# Challenger-2040.net
KiCad netlist of a schematic drawn in EAGLE
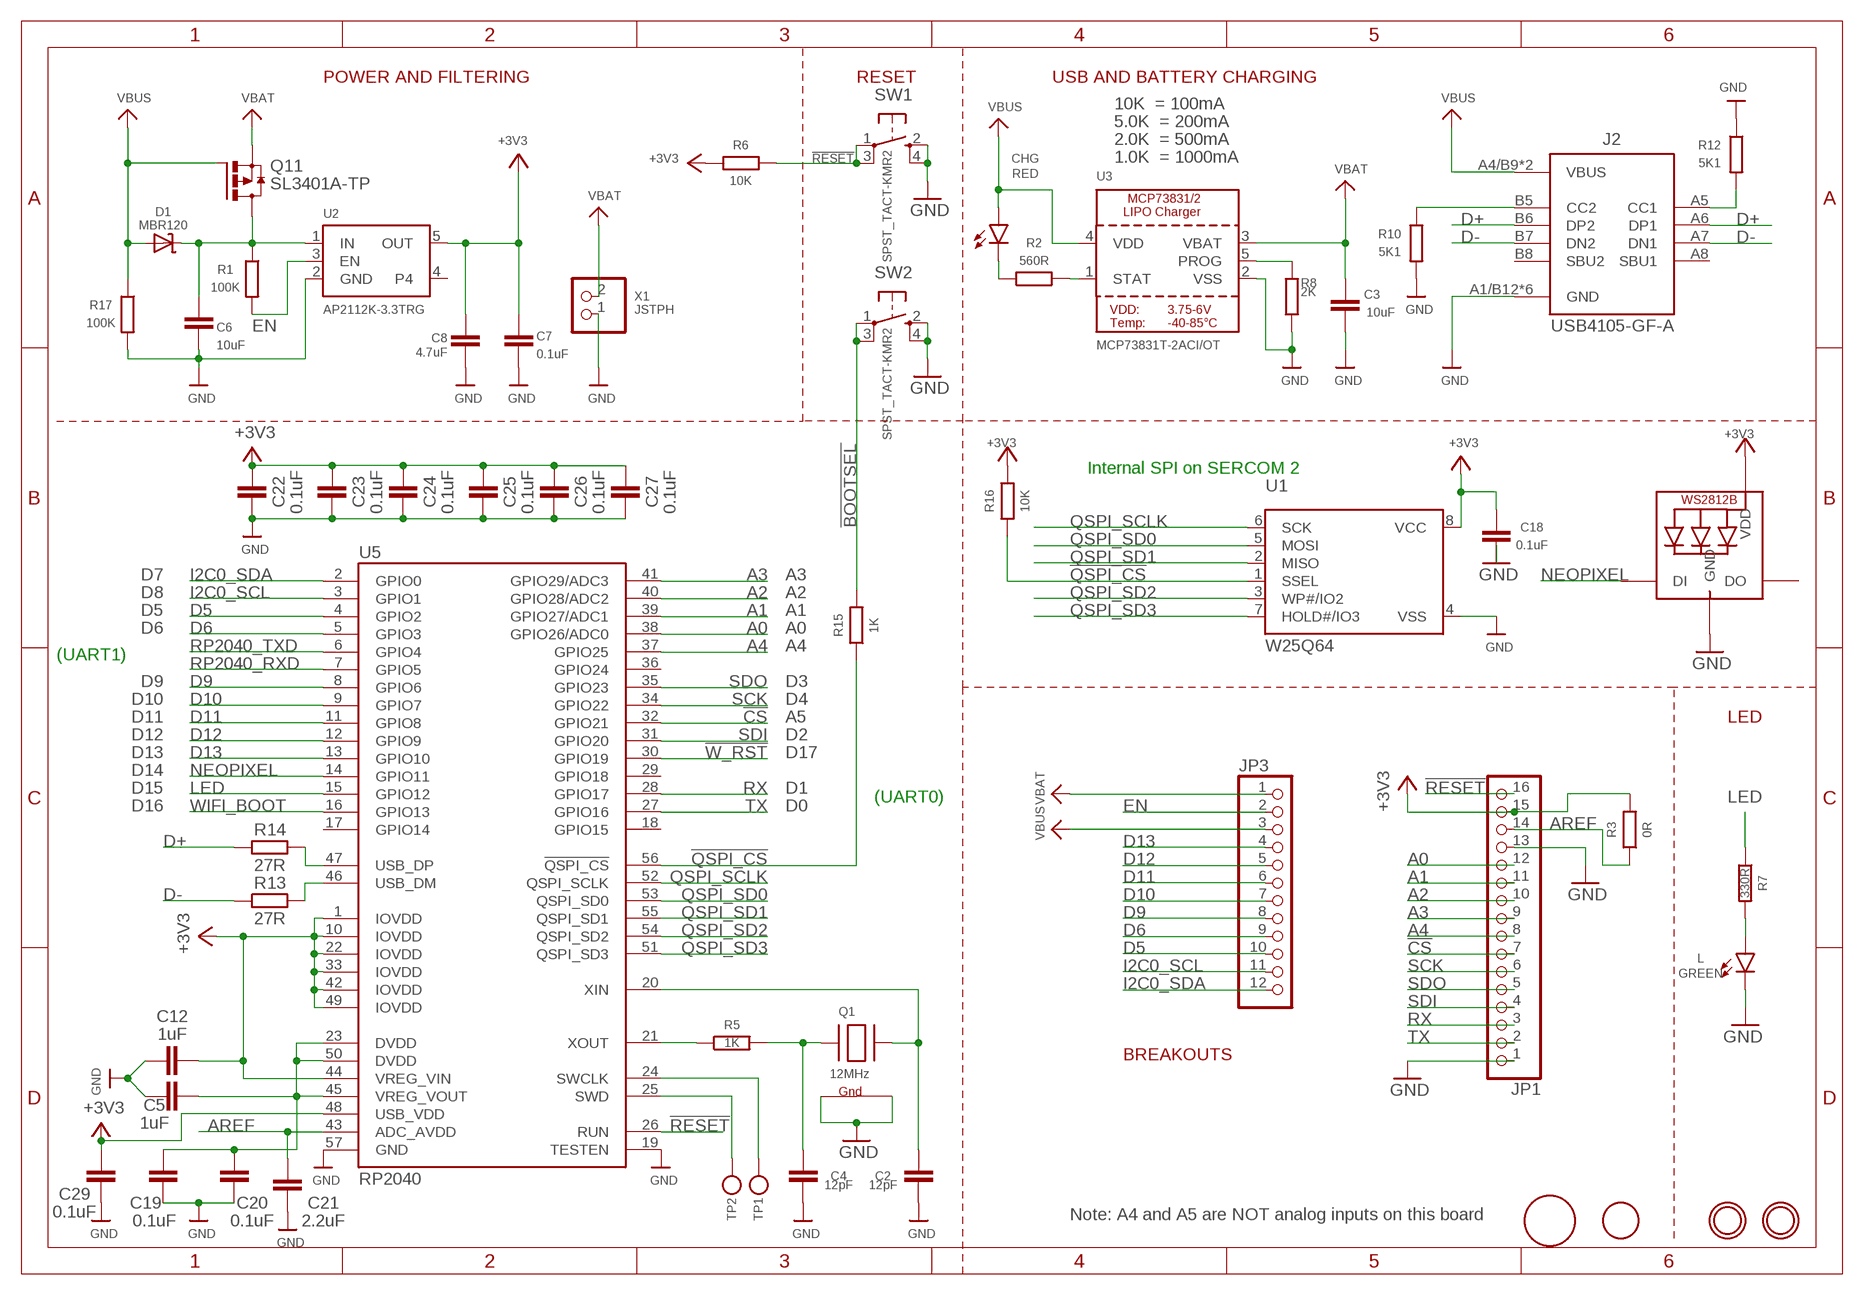
[diagram p0: schematic, sheet 1]
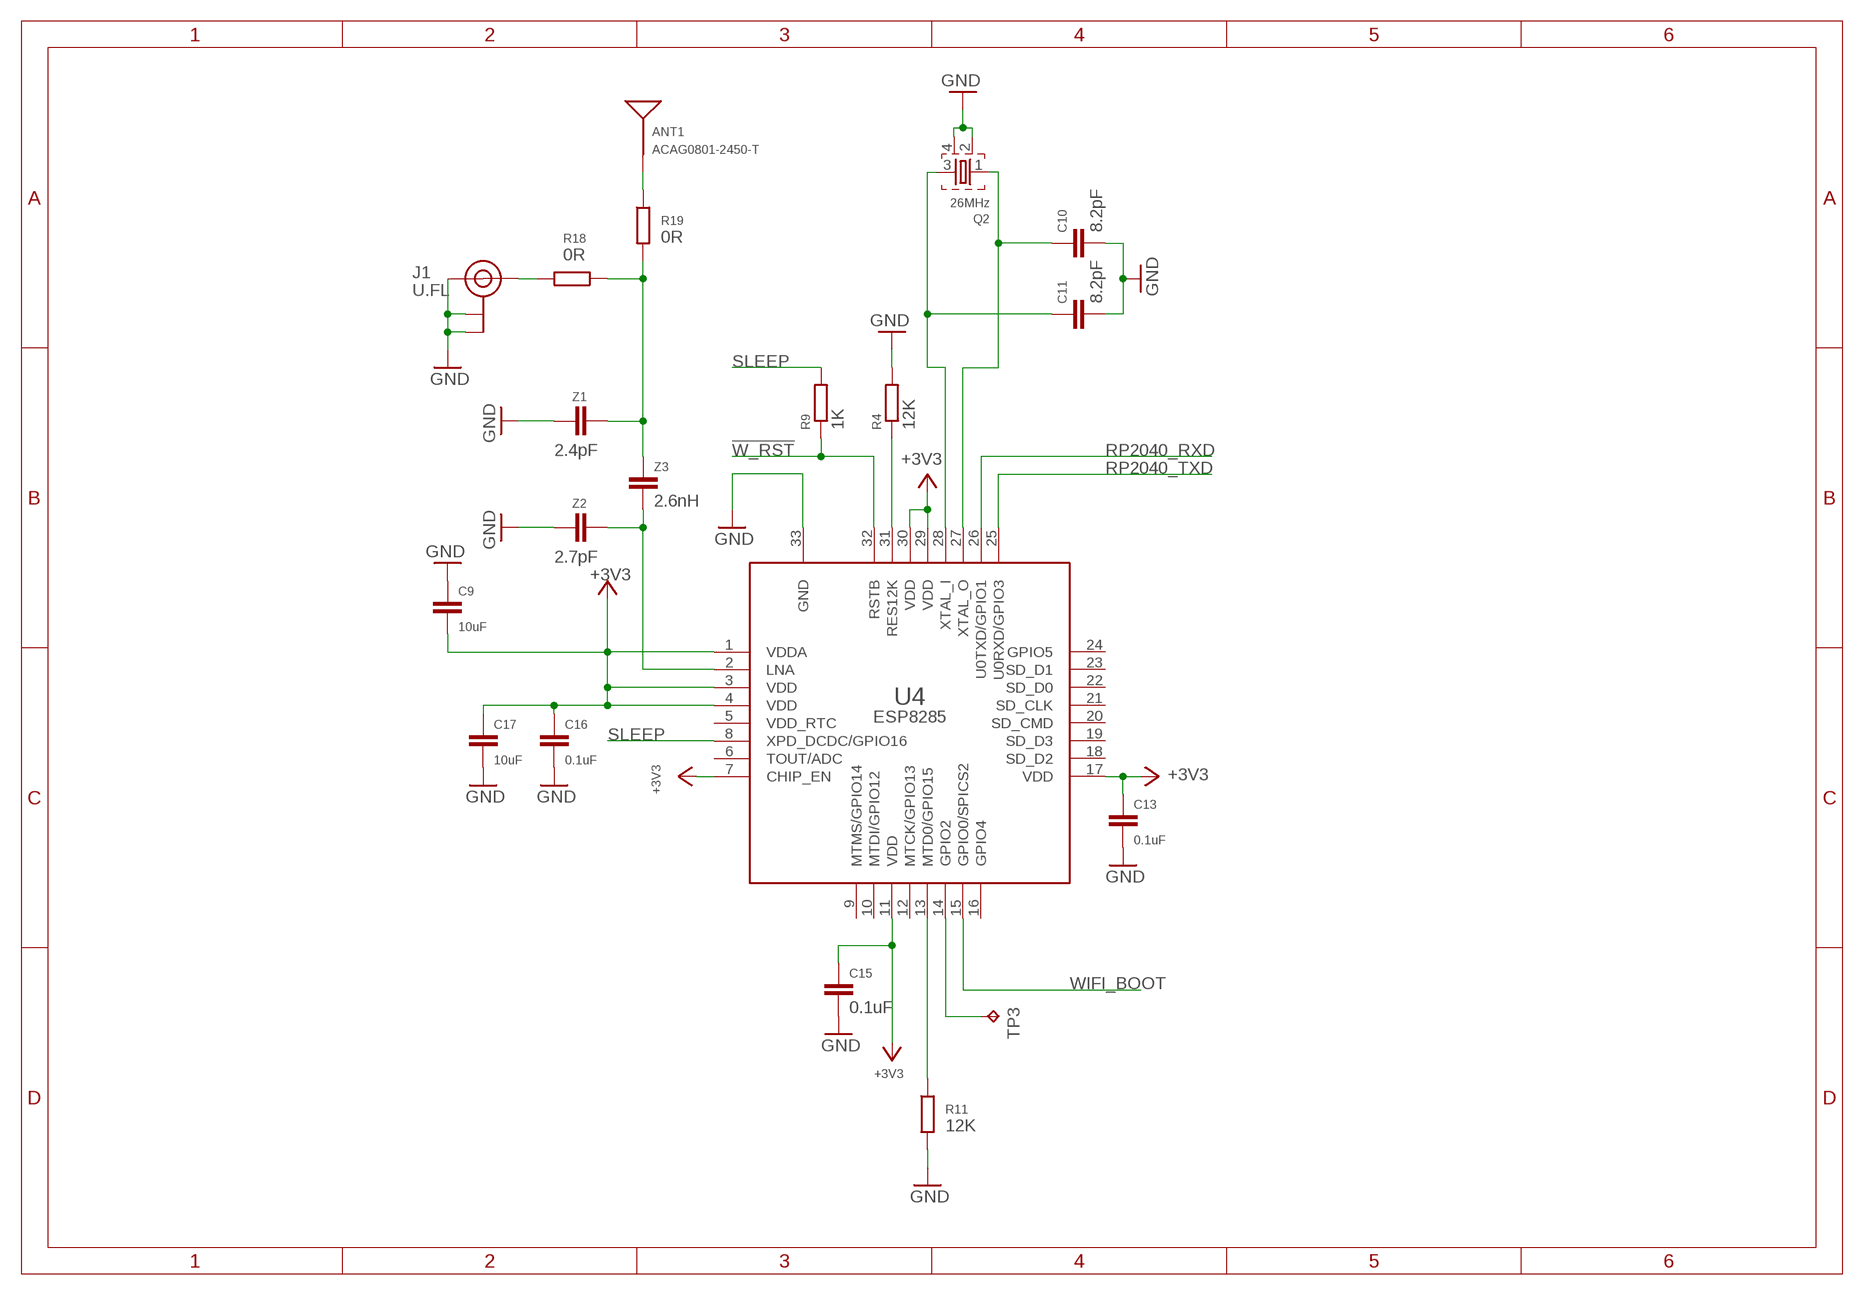
[diagram p1: schematic, sheet 2]

(export (version "E")
  (design (tool "Eeschema 10.0.6"))
  (components
    (comp (ref "C2")
      (value "12pF")
      (footprint "eagle-import:CAPC1005X60")
      (libsource (lib "eagle-import") (part "CCHIP-0402(1005-METRIC)_"))
    )
    (comp (ref "C3")
      (value "10uF")
      (footprint "eagle-import:CAPC1608X85")
      (libsource (lib "eagle-import") (part "CCHIP-0603(1608-METRIC)_"))
    )
    (comp (ref "C4")
      (value "12pF")
      (footprint "eagle-import:CAPC1005X60")
      (libsource (lib "eagle-import") (part "CCHIP-0402(1005-METRIC)_"))
    )
    (comp (ref "C5")
      (value "1uF")
      (footprint "eagle-import:CAPC1005X60")
      (libsource (lib "eagle-import") (part "CCHIP-0402(1005-METRIC)_"))
    )
    (comp (ref "C6")
      (value "10uF")
      (footprint "eagle-import:CAPC1608X85")
      (libsource (lib "eagle-import") (part "CCHIP-0603(1608-METRIC)_"))
    )
    (comp (ref "C7")
      (value "0.1uF")
      (footprint "eagle-import:CAPC1005X60")
      (libsource (lib "eagle-import") (part "CCHIP-0402(1005-METRIC)_"))
    )
    (comp (ref "C8")
      (value "4.7uF")
      (footprint "eagle-import:CAPC1005X60")
      (libsource (lib "eagle-import") (part "CCHIP-0402(1005-METRIC)_"))
    )
    (comp (ref "C12")
      (value "1uF")
      (footprint "eagle-import:CAPC1005X60")
      (libsource (lib "eagle-import") (part "CCHIP-0402(1005-METRIC)_"))
    )
    (comp (ref "C18")
      (value "0.1uF")
      (footprint "eagle-import:CAPC1005X60")
      (libsource (lib "eagle-import") (part "CCHIP-0402(1005-METRIC)_"))
    )
    (comp (ref "C19")
      (value "0.1uF")
      (footprint "eagle-import:CAPC1005X60")
      (libsource (lib "eagle-import") (part "CCHIP-0402(1005-METRIC)_"))
    )
    (comp (ref "C20")
      (value "0.1uF")
      (footprint "eagle-import:CAPC1005X60")
      (libsource (lib "eagle-import") (part "CCHIP-0402(1005-METRIC)_"))
    )
    (comp (ref "C21")
      (value "2.2uF")
      (footprint "eagle-import:CAPC1005X60")
      (libsource (lib "eagle-import") (part "CCHIP-0402(1005-METRIC)_"))
    )
    (comp (ref "C22")
      (value "0.1uF")
      (footprint "eagle-import:CAPC1005X60")
      (libsource (lib "eagle-import") (part "CCHIP-0402(1005-METRIC)_"))
    )
    (comp (ref "C23")
      (value "0.1uF")
      (footprint "eagle-import:CAPC1005X60")
      (libsource (lib "eagle-import") (part "CCHIP-0402(1005-METRIC)_"))
    )
    (comp (ref "C24")
      (value "0.1uF")
      (footprint "eagle-import:CAPC1005X60")
      (libsource (lib "eagle-import") (part "CCHIP-0402(1005-METRIC)_"))
    )
    (comp (ref "C25")
      (value "0.1uF")
      (footprint "eagle-import:CAPC1005X60")
      (libsource (lib "eagle-import") (part "CCHIP-0402(1005-METRIC)_"))
    )
    (comp (ref "C26")
      (value "0.1uF")
      (footprint "eagle-import:CAPC1005X60")
      (libsource (lib "eagle-import") (part "CCHIP-0402(1005-METRIC)_"))
    )
    (comp (ref "C27")
      (value "0.1uF")
      (footprint "eagle-import:CAPC1005X60")
      (libsource (lib "eagle-import") (part "CCHIP-0402(1005-METRIC)_"))
    )
    (comp (ref "C29")
      (value "0.1uF")
      (footprint "eagle-import:CAPC1005X60")
      (libsource (lib "eagle-import") (part "CCHIP-0402(1005-METRIC)_"))
    )
    (comp (ref "CHG")
      (value "RED")
      (footprint "eagle-import:CHIPLED_0603")
      (libsource (lib "eagle-import") (part "LEDCHIPLED_0603"))
    )
    (comp (ref "D1")
      (value "MBR120")
      (footprint "eagle-import:SOD-123")
      (libsource (lib "eagle-import") (part "DIODE-SCHOTTKYSOD-123"))
    )
    (comp (ref "J2")
      (value "USB4105-GF-A")
      (footprint "eagle-import:GCT_USB4105-GF-A")
      (fields (field (name "MF") "GCT"))
      (libsource (lib "eagle-import") (part "USB4105-GF-A"))
    )
    (comp (ref "JP1")
      (value "HEADER-1X16ROUND")
      (footprint "eagle-import:1X16_ROUND")
      (libsource (lib "eagle-import") (part "HEADER-1X16ROUND"))
    )
    (comp (ref "JP3")
      (value "HEADER-1X12")
      (footprint "eagle-import:1X12_ROUND")
      (libsource (lib "eagle-import") (part "HEADER-1X12"))
    )
    (comp (ref "L")
      (value "GREEN")
      (footprint "eagle-import:CHIPLED_0603")
      (libsource (lib "eagle-import") (part "LEDCHIPLED_0603"))
    )
    (comp (ref "LED1")
      (value "SK6812MINI-B")
      (footprint "eagle-import:LED3535")
      (libsource (lib "eagle-import") (part "WS2812B3535"))
    )
    (comp (ref "LOGO1")
      (value "CHALENGER-11MM")
      (footprint "eagle-import:CHALLENGER")
      (libsource (lib "eagle-import") (part "CHALENGER-11MM"))
    )
    (comp (ref "Q1")
      (value "12MHz")
      (footprint "eagle-import:NX3225")
      (libsource (lib "eagle-import") (part "XTAL-4-3225"))
    )
    (comp (ref "Q11")
      (value "SL3401A-TP")
      (footprint "eagle-import:SUPER-SOT3")
      (libsource (lib "eagle-import") (part "FDN360P"))
    )
    (comp (ref "R1")
      (value "100K")
      (footprint "eagle-import:RESC1005X40")
      (libsource (lib "eagle-import") (part "RCHIP-0402(1005-METRIC)_"))
    )
    (comp (ref "R2")
      (value "560R")
      (footprint "eagle-import:RESC1005X40")
      (libsource (lib "eagle-import") (part "RCHIP-0402(1005-METRIC)_"))
    )
    (comp (ref "R3")
      (value "0R")
      (footprint "eagle-import:RESC1005X40")
      (libsource (lib "eagle-import") (part "RCHIP-0402(1005-METRIC)_"))
    )
    (comp (ref "R5")
      (value "1K")
      (footprint "eagle-import:RESC1005X40")
      (libsource (lib "eagle-import") (part "RCHIP-0402(1005-METRIC)_"))
    )
    (comp (ref "R6")
      (value "10K")
      (footprint "eagle-import:RESC1005X40")
      (libsource (lib "eagle-import") (part "RCHIP-0402(1005-METRIC)_"))
    )
    (comp (ref "R7")
      (value "330R")
      (footprint "eagle-import:RESC1005X40")
      (libsource (lib "eagle-import") (part "RCHIP-0402(1005-METRIC)_"))
    )
    (comp (ref "R8")
      (value "2K")
      (footprint "eagle-import:RESC1005X40")
      (libsource (lib "eagle-import") (part "RCHIP-0402(1005-METRIC)_"))
    )
    (comp (ref "R10")
      (value "5K1")
      (footprint "eagle-import:RESC1005X40")
      (libsource (lib "eagle-import") (part "RCHIP-0402(1005-METRIC)_"))
    )
    (comp (ref "R12")
      (value "5K1")
      (footprint "eagle-import:RESC1005X40")
      (libsource (lib "eagle-import") (part "RCHIP-0402(1005-METRIC)_"))
    )
    (comp (ref "R13")
      (value "27R")
      (footprint "eagle-import:RESC1005X40")
      (libsource (lib "eagle-import") (part "RCHIP-0402(1005-METRIC)_"))
    )
    (comp (ref "R14")
      (value "27R")
      (footprint "eagle-import:RESC1005X40")
      (libsource (lib "eagle-import") (part "RCHIP-0402(1005-METRIC)_"))
    )
    (comp (ref "R15")
      (value "1K")
      (footprint "eagle-import:RESC1005X40")
      (libsource (lib "eagle-import") (part "RCHIP-0402(1005-METRIC)_"))
    )
    (comp (ref "R16")
      (value "10K")
      (footprint "eagle-import:RESC1005X40")
      (libsource (lib "eagle-import") (part "RCHIP-0402(1005-METRIC)_"))
    )
    (comp (ref "R17")
      (value "100K")
      (footprint "eagle-import:RESC1005X40")
      (libsource (lib "eagle-import") (part "RCHIP-0402(1005-METRIC)_"))
    )
    (comp (ref "SW1")
      (value "SPST_TACT-KMR2")
      (footprint "eagle-import:KMR2")
      (libsource (lib "eagle-import") (part "SPST_TACT-KMR2"))
    )
    (comp (ref "SW2")
      (value "SPST_TACT-KMR2")
      (footprint "eagle-import:KMR2")
      (libsource (lib "eagle-import") (part "SPST_TACT-KMR2"))
    )
    (comp (ref "TP1")
      (value "TESTPOINTROUND1.5MM")
      (footprint "eagle-import:TESTPOINT_ROUND_1.5MM")
      (libsource (lib "eagle-import") (part "TESTPOINTROUND1.5MM"))
    )
    (comp (ref "TP2")
      (value "TESTPOINTROUND1.5MM")
      (footprint "eagle-import:TESTPOINT_ROUND_1.5MM")
      (libsource (lib "eagle-import") (part "TESTPOINTROUND1.5MM"))
    )
    (comp (ref "U$11")
      (value "CHAL-TEXT")
      (footprint "eagle-import:CHAL-TEXT")
      (libsource (lib "eagle-import") (part "CHAL-TEXT"))
    )
    (comp (ref "U$31")
      (value "MOUNTINGHOLE2.5")
      (footprint "eagle-import:MOUNTINGHOLE_2.5_PLATED")
      (libsource (lib "eagle-import") (part "MOUNTINGHOLE2.5"))
    )
    (comp (ref "U$32")
      (value "MOUNTINGHOLE2.5")
      (footprint "eagle-import:MOUNTINGHOLE_2.5_PLATED")
      (libsource (lib "eagle-import") (part "MOUNTINGHOLE2.5"))
    )
    (comp (ref "U1")
      (value "W25Q64")
      (footprint "eagle-import:SOIC8_208MIL")
      (libsource (lib "eagle-import") (part "SPIFLASH_SOIC8208MIL"))
    )
    (comp (ref "U2")
      (value "AP2112K-3.3TRG")
      (footprint "eagle-import:SOT23-5")
      (libsource (lib "eagle-import") (part "VREG_SOT23-5"))
    )
    (comp (ref "U3")
      (value "MCP73831T-2ACI/OT")
      (footprint "eagle-import:SOT23-5")
      (libsource (lib "eagle-import") (part "MCP73831/2"))
    )
    (comp (ref "U5")
      (value "RP2040")
      (footprint "eagle-import:QFN40P700X700X90-57T310N")
      (libsource (lib "eagle-import") (part "RP2040"))
    )
    (comp (ref "X1")
      (value "JSTPH")
      (footprint "eagle-import:JSTPH2")
      (libsource (lib "eagle-import") (part "CON_JST_PH_2PIN"))
    )
    (comp (ref "ANT1")
      (value "ACAG0801-2450-T")
      (footprint "eagle-import:ANTENNA-CHIP6")
      (libsource (lib "eagle-import") (part "ANTENNA2SMD6"))
    )
    (comp (ref "C9")
      (value "10uF")
      (footprint "eagle-import:CAPC1608X85")
      (libsource (lib "eagle-import") (part "CCHIP-0603(1608-METRIC)_"))
    )
    (comp (ref "C10")
      (value "8.2pF")
      (footprint "eagle-import:CAPC1005X60")
      (libsource (lib "eagle-import") (part "CCHIP-0402(1005-METRIC)_"))
    )
    (comp (ref "C11")
      (value "8.2pF")
      (footprint "eagle-import:CAPC1005X60")
      (libsource (lib "eagle-import") (part "CCHIP-0402(1005-METRIC)_"))
    )
    (comp (ref "C13")
      (value "0.1uF")
      (footprint "eagle-import:CAPC1005X60")
      (libsource (lib "eagle-import") (part "CCHIP-0402(1005-METRIC)_"))
    )
    (comp (ref "C15")
      (value "0.1uF")
      (footprint "eagle-import:CAPC1005X60")
      (libsource (lib "eagle-import") (part "CCHIP-0402(1005-METRIC)_"))
    )
    (comp (ref "C16")
      (value "0.1uF")
      (footprint "eagle-import:CAPC1005X60")
      (libsource (lib "eagle-import") (part "CCHIP-0402(1005-METRIC)_"))
    )
    (comp (ref "C17")
      (value "10uF")
      (footprint "eagle-import:CAPC1608X85")
      (libsource (lib "eagle-import") (part "CCHIP-0603(1608-METRIC)_"))
    )
    (comp (ref "J1")
      (value "U.FL")
      (footprint "eagle-import:U.FL")
      (libsource (lib "eagle-import") (part "U.FL"))
    )
    (comp (ref "Q2")
      (value "26MHz")
      (footprint "eagle-import:FA-128")
      (libsource (lib "eagle-import") (part "FA-128"))
    )
    (comp (ref "R4")
      (value "12K")
      (footprint "eagle-import:RESC1005X40")
      (libsource (lib "eagle-import") (part "RCHIP-0402(1005-METRIC)_"))
    )
    (comp (ref "R9")
      (value "1K")
      (footprint "eagle-import:RESC1005X40")
      (libsource (lib "eagle-import") (part "RCHIP-0402(1005-METRIC)_"))
    )
    (comp (ref "R11")
      (value "12K")
      (footprint "eagle-import:RESC1005X40")
      (libsource (lib "eagle-import") (part "RCHIP-0402(1005-METRIC)_"))
    )
    (comp (ref "R18")
      (value "0R")
      (footprint "eagle-import:RESC1005X40")
      (libsource (lib "eagle-import") (part "RCHIP-0402(1005-METRIC)_"))
    )
    (comp (ref "R19")
      (value "0R")
      (footprint "eagle-import:RESC1005X40")
      (libsource (lib "eagle-import") (part "RCHIP-0402(1005-METRIC)_"))
    )
    (comp (ref "TP3")
      (value "TPB1,27")
      (footprint "eagle-import:B1,27")
      (libsource (lib "eagle-import") (part "TPB1,27"))
    )
    (comp (ref "U4")
      (value "ESP8285")
      (footprint "eagle-import:SLP32")
      (libsource (lib "eagle-import") (part "ESP8266EXT"))
    )
    (comp (ref "Z1")
      (value "2.4pF")
      (footprint "eagle-import:CAPC1005X60")
      (libsource (lib "eagle-import") (part "CCHIP-0402(1005-METRIC)_"))
    )
    (comp (ref "Z2")
      (value "2.7pF")
      (footprint "eagle-import:CAPC1005X60")
      (libsource (lib "eagle-import") (part "CCHIP-0402(1005-METRIC)_"))
    )
    (comp (ref "Z3")
      (value "2.6nH")
      (footprint "eagle-import:CAPC1005X60")
      (libsource (lib "eagle-import") (part "CCHIP-0402(1005-METRIC)_"))
    )
  )
  (nets
    (net (code "1") (name "+3V3") (class "Default")
      (node (ref "C12") (pin "2") (pinfunction "2_2") (pintype "passive"))
      (node (ref "C13") (pin "1") (pinfunction "1_1") (pintype "passive"))
      (node (ref "C15") (pin "1") (pinfunction "1_1") (pintype "passive"))
      (node (ref "C16") (pin "1") (pinfunction "1_1") (pintype "passive"))
      (node (ref "C17") (pin "1") (pinfunction "1_1") (pintype "passive"))
      (node (ref "C18") (pin "1") (pinfunction "1_1") (pintype "passive"))
      (node (ref "C22") (pin "2") (pinfunction "2_2") (pintype "passive"))
      (node (ref "C23") (pin "2") (pinfunction "2_2") (pintype "passive"))
      (node (ref "C24") (pin "2") (pinfunction "2_2") (pintype "passive"))
      (node (ref "C25") (pin "2") (pinfunction "2_2") (pintype "passive"))
      (node (ref "C26") (pin "2") (pinfunction "2_2") (pintype "passive"))
      (node (ref "C27") (pin "2") (pinfunction "2_2") (pintype "passive"))
      (node (ref "C29") (pin "2") (pinfunction "2_2") (pintype "passive"))
      (node (ref "C7") (pin "1") (pinfunction "1_1") (pintype "passive"))
      (node (ref "C8") (pin "1") (pinfunction "1_1") (pintype "passive"))
      (node (ref "C9") (pin "2") (pinfunction "2_2") (pintype "passive"))
      (node (ref "JP1") (pin "15") (pinfunction "15_15") (pintype "passive"))
      (node (ref "LED1") (pin "2") (pinfunction "VDD_2") (pintype "power_in"))
      (node (ref "R16") (pin "1") (pinfunction "1_1") (pintype "passive"))
      (node (ref "R3") (pin "2") (pinfunction "2_2") (pintype "passive"))
      (node (ref "R6") (pin "2") (pinfunction "2_2") (pintype "passive"))
      (node (ref "U1") (pin "8") (pinfunction "VCC_8") (pintype "bidirectional"))
      (node (ref "U2") (pin "5") (pinfunction "OUT_5") (pintype "power_in"))
      (node (ref "U4") (pin "1") (pinfunction "VDDA_1") (pintype "bidirectional"))
      (node (ref "U4") (pin "11") (pinfunction "VDD_11") (pintype "bidirectional"))
      (node (ref "U4") (pin "17") (pinfunction "VDD_17") (pintype "bidirectional"))
      (node (ref "U4") (pin "29") (pinfunction "VDD_29") (pintype "bidirectional"))
      (node (ref "U4") (pin "3") (pinfunction "VDD_3") (pintype "bidirectional"))
      (node (ref "U4") (pin "30") (pinfunction "VDD_30") (pintype "bidirectional"))
      (node (ref "U4") (pin "4") (pinfunction "VDD_4") (pintype "bidirectional"))
      (node (ref "U4") (pin "7") (pinfunction "CHIP_EN_7") (pintype "bidirectional"))
      (node (ref "U5") (pin "1") (pinfunction "IOVDD_1") (pintype "bidirectional"))
      (node (ref "U5") (pin "10") (pinfunction "IOVDD_10") (pintype "bidirectional"))
      (node (ref "U5") (pin "22") (pinfunction "IOVDD_22") (pintype "bidirectional"))
      (node (ref "U5") (pin "33") (pinfunction "IOVDD_33") (pintype "bidirectional"))
      (node (ref "U5") (pin "42") (pinfunction "IOVDD_42") (pintype "bidirectional"))
      (node (ref "U5") (pin "44") (pinfunction "VREG_VIN_44") (pintype "bidirectional"))
      (node (ref "U5") (pin "48") (pinfunction "USB_VDD_48") (pintype "bidirectional"))
      (node (ref "U5") (pin "49") (pinfunction "IOVDD_49") (pintype "bidirectional"))
    )
    (net (code "2") (name "A0") (class "Default")
      (node (ref "JP1") (pin "12") (pinfunction "12_12") (pintype "passive"))
      (node (ref "U5") (pin "38") (pinfunction "GPIO26/ADC0_38") (pintype "bidirectional"))
    )
    (net (code "3") (name "A1") (class "Default")
      (node (ref "JP1") (pin "11") (pinfunction "11_11") (pintype "passive"))
      (node (ref "U5") (pin "39") (pinfunction "GPIO27/ADC1_39") (pintype "bidirectional"))
    )
    (net (code "4") (name "A2") (class "Default")
      (node (ref "JP1") (pin "10") (pinfunction "10_10") (pintype "passive"))
      (node (ref "U5") (pin "40") (pinfunction "GPIO28/ADC2_40") (pintype "bidirectional"))
    )
    (net (code "5") (name "A3") (class "Default")
      (node (ref "JP1") (pin "9") (pinfunction "9_9") (pintype "passive"))
      (node (ref "U5") (pin "41") (pinfunction "GPIO29/ADC3_41") (pintype "bidirectional"))
    )
    (net (code "6") (name "A4") (class "Default")
      (node (ref "JP1") (pin "8") (pinfunction "8_8") (pintype "passive"))
      (node (ref "U5") (pin "37") (pinfunction "GPIO25_37") (pintype "bidirectional"))
    )
    (net (code "7") (name "AREF") (class "Default")
      (node (ref "C21") (pin "2") (pinfunction "2_2") (pintype "passive"))
      (node (ref "JP1") (pin "14") (pinfunction "14_14") (pintype "passive"))
      (node (ref "R3") (pin "1") (pinfunction "1_1") (pintype "passive"))
      (node (ref "U5") (pin "43") (pinfunction "ADC_AVDD_43") (pintype "bidirectional"))
    )
    (net (code "8") (name "D+") (class "Default")
      (node (ref "J2") (pin "A6") (pinfunction "DP1_A6") (pintype "bidirectional"))
      (node (ref "J2") (pin "B6") (pinfunction "DP2_B6") (pintype "bidirectional"))
      (node (ref "R14") (pin "1") (pinfunction "1_1") (pintype "passive"))
    )
    (net (code "9") (name "D-") (class "Default")
      (node (ref "J2") (pin "A7") (pinfunction "DN1_A7") (pintype "bidirectional"))
      (node (ref "J2") (pin "B7") (pinfunction "DN2_B7") (pintype "bidirectional"))
      (node (ref "R13") (pin "1") (pinfunction "1_1") (pintype "passive"))
    )
    (net (code "10") (name "D5") (class "Default")
      (node (ref "JP3") (pin "10") (pinfunction "10_10") (pintype "passive"))
      (node (ref "U5") (pin "4") (pinfunction "GPIO2_4") (pintype "bidirectional"))
    )
    (net (code "11") (name "D6") (class "Default")
      (node (ref "JP3") (pin "9") (pinfunction "9_9") (pintype "passive"))
      (node (ref "U5") (pin "5") (pinfunction "GPIO3_5") (pintype "bidirectional"))
    )
    (net (code "12") (name "D9") (class "Default")
      (node (ref "JP3") (pin "8") (pinfunction "8_8") (pintype "passive"))
      (node (ref "U5") (pin "8") (pinfunction "GPIO6_8") (pintype "bidirectional"))
    )
    (net (code "13") (name "D10") (class "Default")
      (node (ref "JP3") (pin "7") (pinfunction "7_7") (pintype "passive"))
      (node (ref "U5") (pin "9") (pinfunction "GPIO7_9") (pintype "bidirectional"))
    )
    (net (code "14") (name "D11") (class "Default")
      (node (ref "JP3") (pin "6") (pinfunction "6_6") (pintype "passive"))
      (node (ref "U5") (pin "11") (pinfunction "GPIO8_11") (pintype "bidirectional"))
    )
    (net (code "15") (name "D12") (class "Default")
      (node (ref "JP3") (pin "5") (pinfunction "5_5") (pintype "passive"))
      (node (ref "U5") (pin "12") (pinfunction "GPIO9_12") (pintype "bidirectional"))
    )
    (net (code "16") (name "D13") (class "Default")
      (node (ref "JP3") (pin "4") (pinfunction "4_4") (pintype "passive"))
      (node (ref "U5") (pin "13") (pinfunction "GPIO10_13") (pintype "bidirectional"))
    )
    (net (code "17") (name "EN") (class "Default")
      (node (ref "JP3") (pin "2") (pinfunction "2_2") (pintype "passive"))
      (node (ref "R1") (pin "2") (pinfunction "2_2") (pintype "passive"))
      (node (ref "U2") (pin "3") (pinfunction "EN_3") (pintype "input"))
    )
    (net (code "18") (name "GND") (class "Default")
      (node (ref "C10") (pin "2") (pinfunction "2_2") (pintype "passive"))
      (node (ref "C11") (pin "2") (pinfunction "2_2") (pintype "passive"))
      (node (ref "C12") (pin "1") (pinfunction "1_1") (pintype "passive"))
      (node (ref "C13") (pin "2") (pinfunction "2_2") (pintype "passive"))
      (node (ref "C15") (pin "2") (pinfunction "2_2") (pintype "passive"))
      (node (ref "C16") (pin "2") (pinfunction "2_2") (pintype "passive"))
      (node (ref "C17") (pin "2") (pinfunction "2_2") (pintype "passive"))
      (node (ref "C18") (pin "2") (pinfunction "2_2") (pintype "passive"))
      (node (ref "C19") (pin "1") (pinfunction "1_1") (pintype "passive"))
      (node (ref "C2") (pin "2") (pinfunction "2_2") (pintype "passive"))
      (node (ref "C20") (pin "1") (pinfunction "1_1") (pintype "passive"))
      (node (ref "C21") (pin "1") (pinfunction "1_1") (pintype "passive"))
      (node (ref "C22") (pin "1") (pinfunction "1_1") (pintype "passive"))
      (node (ref "C23") (pin "1") (pinfunction "1_1") (pintype "passive"))
      (node (ref "C24") (pin "1") (pinfunction "1_1") (pintype "passive"))
      (node (ref "C25") (pin "1") (pinfunction "1_1") (pintype "passive"))
      (node (ref "C26") (pin "1") (pinfunction "1_1") (pintype "passive"))
      (node (ref "C27") (pin "1") (pinfunction "1_1") (pintype "passive"))
      (node (ref "C29") (pin "1") (pinfunction "1_1") (pintype "passive"))
      (node (ref "C3") (pin "2") (pinfunction "2_2") (pintype "passive"))
      (node (ref "C4") (pin "2") (pinfunction "2_2") (pintype "passive"))
      (node (ref "C5") (pin "1") (pinfunction "1_1") (pintype "passive"))
      (node (ref "C6") (pin "2") (pinfunction "2_2") (pintype "passive"))
      (node (ref "C7") (pin "2") (pinfunction "2_2") (pintype "passive"))
      (node (ref "C8") (pin "2") (pinfunction "2_2") (pintype "passive"))
      (node (ref "C9") (pin "1") (pinfunction "1_1") (pintype "passive"))
      (node (ref "J1") (pin "P$1") (pinfunction "GND_P$1") (pintype "bidirectional"))
      (node (ref "J1") (pin "P$2") (pinfunction "GND_P$2") (pintype "bidirectional"))
      (node (ref "J1") (pin "P$4") (pinfunction "PT_P$4") (pintype "bidirectional"))
      (node (ref "J2") (pin "A1/B12") (pinfunction "GND_A1/B12") (pintype "power_in"))
      (node (ref "J2") (pin "B1/A12") (pinfunction "GND_B1/A12") (pintype "power_in"))
      (node (ref "J2") (pin "G1") (pinfunction "GND_G1") (pintype "power_in"))
      (node (ref "J2") (pin "G2") (pinfunction "GND_G2") (pintype "power_in"))
      (node (ref "J2") (pin "G3") (pinfunction "GND_G3") (pintype "power_in"))
      (node (ref "J2") (pin "G4") (pinfunction "GND_G4") (pintype "power_in"))
      (node (ref "JP1") (pin "1") (pinfunction "1_1") (pintype "passive"))
      (node (ref "JP1") (pin "13") (pinfunction "13_13") (pintype "passive"))
      (node (ref "L") (pin "C") (pinfunction "C_C") (pintype "passive"))
      (node (ref "LED1") (pin "4") (pinfunction "GND_4") (pintype "power_in"))
      (node (ref "Q1") (pin "2") (pinfunction "G2_2") (pintype "power_in"))
      (node (ref "Q1") (pin "4") (pinfunction "G1_4") (pintype "power_in"))
      (node (ref "Q2") (pin "2") (pinfunction "2_2") (pintype "passive"))
      (node (ref "Q2") (pin "4") (pinfunction "4_4") (pintype "passive"))
      (node (ref "R10") (pin "2") (pinfunction "2_2") (pintype "passive"))
      (node (ref "R11") (pin "2") (pinfunction "2_2") (pintype "passive"))
      (node (ref "R12") (pin "1") (pinfunction "1_1") (pintype "passive"))
      (node (ref "R17") (pin "2") (pinfunction "2_2") (pintype "passive"))
      (node (ref "R4") (pin "2") (pinfunction "2_2") (pintype "passive"))
      (node (ref "R8") (pin "2") (pinfunction "2_2") (pintype "passive"))
      (node (ref "SW1") (pin "2") (pinfunction "S_2") (pintype "passive"))
      (node (ref "SW1") (pin "4") (pinfunction "S1_4") (pintype "passive"))
      (node (ref "SW2") (pin "2") (pinfunction "S_2") (pintype "passive"))
      (node (ref "SW2") (pin "4") (pinfunction "S1_4") (pintype "passive"))
      (node (ref "U1") (pin "4") (pinfunction "VSS_4") (pintype "bidirectional"))
      (node (ref "U2") (pin "2") (pinfunction "GND_2") (pintype "power_in"))
      (node (ref "U3") (pin "2") (pinfunction "VSS_2") (pintype "power_in"))
      (node (ref "U4") (pin "33") (pinfunction "GND_33") (pintype "bidirectional"))
      (node (ref "U5") (pin "19") (pinfunction "TESTEN_19") (pintype "bidirectional"))
      (node (ref "U5") (pin "57") (pinfunction "GND_57") (pintype "bidirectional"))
      (node (ref "X1") (pin "1") (pinfunction "1_1") (pintype "passive"))
      (node (ref "Z1") (pin "1") (pinfunction "1_1") (pintype "passive"))
      (node (ref "Z2") (pin "1") (pinfunction "1_1") (pintype "passive"))
    )
    (net (code "19") (name "I2C0_SCL") (class "Default")
      (node (ref "JP3") (pin "11") (pinfunction "11_11") (pintype "passive"))
      (node (ref "U5") (pin "3") (pinfunction "GPIO1_3") (pintype "bidirectional"))
    )
    (net (code "20") (name "I2C0_SDA") (class "Default")
      (node (ref "JP3") (pin "12") (pinfunction "12_12") (pintype "passive"))
      (node (ref "U5") (pin "2") (pinfunction "GPIO0_2") (pintype "bidirectional"))
    )
    (net (code "21") (name "LED") (class "Default")
      (node (ref "R7") (pin "1") (pinfunction "1_1") (pintype "passive"))
      (node (ref "U5") (pin "15") (pinfunction "GPIO12_15") (pintype "bidirectional"))
    )
    (net (code "22") (name "NEOPIXEL") (class "Default")
      (node (ref "LED1") (pin "1") (pinfunction "DI_1") (pintype "input"))
      (node (ref "U5") (pin "14") (pinfunction "GPIO11_14") (pintype "bidirectional"))
    )
    (net (code "23") (name "Net-(ANT1-SIGNAL)") (class "Default")
      (node (ref "ANT1") (pin "1") (pinfunction "SIGNAL_1") (pintype "bidirectional"))
      (node (ref "R19") (pin "1") (pinfunction "1_1") (pintype "passive"))
    )
    (net (code "24") (name "Net-(CHG-PadC)") (class "Default")
      (node (ref "CHG") (pin "C") (pinfunction "C_C") (pintype "passive"))
      (node (ref "R2") (pin "1") (pinfunction "1_1") (pintype "passive"))
    )
    (net (code "25") (name "Net-(J1-SIGNAL)") (class "Default")
      (node (ref "J1") (pin "P$3") (pinfunction "SIGNAL_P$3") (pintype "bidirectional"))
      (node (ref "R18") (pin "2") (pinfunction "2_2") (pintype "passive"))
    )
    (net (code "26") (name "Net-(J2-CC1)") (class "Default")
      (node (ref "J2") (pin "A5") (pinfunction "CC1_A5") (pintype "bidirectional"))
      (node (ref "R12") (pin "2") (pinfunction "2_2") (pintype "passive"))
    )
    (net (code "27") (name "Net-(J2-CC2)") (class "Default")
      (node (ref "J2") (pin "B5") (pinfunction "CC2_B5") (pintype "bidirectional"))
      (node (ref "R10") (pin "1") (pinfunction "1_1") (pintype "passive"))
    )
    (net (code "28") (name "Net-(L-PadA)") (class "Default")
      (node (ref "L") (pin "A") (pinfunction "A_A") (pintype "passive"))
      (node (ref "R7") (pin "2") (pinfunction "2_2") (pintype "passive"))
    )
    (net (code "29") (name "Net-(Q1-X1)") (class "Default")
      (node (ref "C4") (pin "1") (pinfunction "1_1") (pintype "passive"))
      (node (ref "Q1") (pin "1") (pinfunction "X1_1") (pintype "bidirectional"))
      (node (ref "R5") (pin "2") (pinfunction "2_2") (pintype "passive"))
    )
    (net (code "30") (name "Net-(Q1-X2)") (class "Default")
      (node (ref "C2") (pin "1") (pinfunction "1_1") (pintype "passive"))
      (node (ref "Q1") (pin "3") (pinfunction "X2_3") (pintype "bidirectional"))
      (node (ref "U5") (pin "20") (pinfunction "XIN_20") (pintype "bidirectional"))
    )
    (net (code "31") (name "Net-(Q11-D)") (class "Default")
      (node (ref "C6") (pin "1") (pinfunction "1_1") (pintype "passive"))
      (node (ref "D1") (pin "C") (pinfunction "C_C") (pintype "passive"))
      (node (ref "Q11") (pin "3") (pinfunction "D_3") (pintype "passive"))
      (node (ref "R1") (pin "1") (pinfunction "1_1") (pintype "passive"))
      (node (ref "U2") (pin "1") (pinfunction "IN_1") (pintype "power_in"))
    )
    (net (code "32") (name "Net-(R18-Pad1)") (class "Default")
      (node (ref "R18") (pin "1") (pinfunction "1_1") (pintype "passive"))
      (node (ref "R19") (pin "2") (pinfunction "2_2") (pintype "passive"))
      (node (ref "Z1") (pin "2") (pinfunction "2_2") (pintype "passive"))
      (node (ref "Z3") (pin "1") (pinfunction "1_1") (pintype "passive"))
    )
    (net (code "33") (name "Net-(U3-PROG)") (class "Default")
      (node (ref "R8") (pin "1") (pinfunction "1_1") (pintype "passive"))
      (node (ref "U3") (pin "5") (pinfunction "PROG_5") (pintype "input"))
    )
    (net (code "34") (name "Net-(U3-STAT)") (class "Default")
      (node (ref "R2") (pin "2") (pinfunction "2_2") (pintype "passive"))
      (node (ref "U3") (pin "1") (pinfunction "STAT_1") (pintype "output"))
    )
    (net (code "35") (name "Net-(U4-GPIO2)") (class "Default")
      (node (ref "TP3") (pin "TP") (pinfunction "TP_TP") (pintype "input"))
      (node (ref "U4") (pin "14") (pinfunction "GPIO2_14") (pintype "bidirectional"))
    )
    (net (code "36") (name "Net-(U4-LNA)") (class "Default")
      (node (ref "U4") (pin "2") (pinfunction "LNA_2") (pintype "bidirectional"))
      (node (ref "Z2") (pin "2") (pinfunction "2_2") (pintype "passive"))
      (node (ref "Z3") (pin "2") (pinfunction "2_2") (pintype "passive"))
    )
    (net (code "37") (name "Net-(U4-MTD0{slash}GPIO15)") (class "Default")
      (node (ref "R11") (pin "1") (pinfunction "1_1") (pintype "passive"))
      (node (ref "U4") (pin "13") (pinfunction "MTD0/GPIO15_13") (pintype "bidirectional"))
    )
    (net (code "38") (name "Net-(U4-RES12K)") (class "Default")
      (node (ref "R4") (pin "1") (pinfunction "1_1") (pintype "passive"))
      (node (ref "U4") (pin "31") (pinfunction "RES12K_31") (pintype "bidirectional"))
    )
    (net (code "39") (name "Net-(U4-XTAL_I)") (class "Default")
      (node (ref "C11") (pin "1") (pinfunction "1_1") (pintype "passive"))
      (node (ref "Q2") (pin "3") (pinfunction "3_3") (pintype "passive"))
      (node (ref "U4") (pin "28") (pinfunction "XTAL_I_28") (pintype "bidirectional"))
    )
    (net (code "40") (name "Net-(U4-XTAL_O)") (class "Default")
      (node (ref "C10") (pin "1") (pinfunction "1_1") (pintype "passive"))
      (node (ref "Q2") (pin "1") (pinfunction "1_1") (pintype "passive"))
      (node (ref "U4") (pin "27") (pinfunction "XTAL_O_27") (pintype "bidirectional"))
    )
    (net (code "41") (name "Net-(U5-SWCLK)") (class "Default")
      (node (ref "TP1") (pin "P$1") (pinfunction "P$1_P$1") (pintype "bidirectional"))
      (node (ref "U5") (pin "24") (pinfunction "SWCLK_24") (pintype "bidirectional"))
    )
    (net (code "42") (name "Net-(U5-SWD)") (class "Default")
      (node (ref "TP2") (pin "P$1") (pinfunction "P$1_P$1") (pintype "bidirectional"))
      (node (ref "U5") (pin "25") (pinfunction "SWD_25") (pintype "bidirectional"))
    )
    (net (code "43") (name "Net-(U5-USB_DM)") (class "Default")
      (node (ref "R13") (pin "2") (pinfunction "2_2") (pintype "passive"))
      (node (ref "U5") (pin "46") (pinfunction "USB_DM_46") (pintype "bidirectional"))
    )
    (net (code "44") (name "Net-(U5-USB_DP)") (class "Default")
      (node (ref "R14") (pin "2") (pinfunction "2_2") (pintype "passive"))
      (node (ref "U5") (pin "47") (pinfunction "USB_DP_47") (pintype "bidirectional"))
    )
    (net (code "45") (name "Net-(U5-VREG_VOUT)") (class "Default")
      (node (ref "C19") (pin "2") (pinfunction "2_2") (pintype "passive"))
      (node (ref "C20") (pin "2") (pinfunction "2_2") (pintype "passive"))
      (node (ref "C5") (pin "2") (pinfunction "2_2") (pintype "passive"))
      (node (ref "U5") (pin "23") (pinfunction "DVDD_23") (pintype "bidirectional"))
      (node (ref "U5") (pin "45") (pinfunction "VREG_VOUT_45") (pintype "bidirectional"))
      (node (ref "U5") (pin "50") (pinfunction "DVDD_50") (pintype "bidirectional"))
    )
    (net (code "46") (name "Net-(U5-XOUT)") (class "Default")
      (node (ref "R5") (pin "1") (pinfunction "1_1") (pintype "passive"))
      (node (ref "U5") (pin "21") (pinfunction "XOUT_21") (pintype "bidirectional"))
    )
    (net (code "47") (name "QSPI_SCLK") (class "Default")
      (node (ref "U1") (pin "6") (pinfunction "SCK_6") (pintype "bidirectional"))
      (node (ref "U5") (pin "52") (pinfunction "QSPI_SCLK_52") (pintype "bidirectional"))
    )
    (net (code "48") (name "QSPI_SD0") (class "Default")
      (node (ref "U1") (pin "5") (pinfunction "MOSI_5") (pintype "bidirectional"))
      (node (ref "U5") (pin "53") (pinfunction "QSPI_SD0_53") (pintype "bidirectional"))
    )
    (net (code "49") (name "QSPI_SD1") (class "Default")
      (node (ref "U1") (pin "2") (pinfunction "MISO_2") (pintype "bidirectional"))
      (node (ref "U5") (pin "55") (pinfunction "QSPI_SD1_55") (pintype "bidirectional"))
    )
    (net (code "50") (name "QSPI_SD2") (class "Default")
      (node (ref "U1") (pin "3") (pinfunction "WP#/IO2_3") (pintype "bidirectional"))
      (node (ref "U5") (pin "54") (pinfunction "QSPI_SD2_54") (pintype "bidirectional"))
    )
    (net (code "51") (name "QSPI_SD3") (class "Default")
      (node (ref "U1") (pin "7") (pinfunction "HOLD#/IO3_7") (pintype "bidirectional"))
      (node (ref "U5") (pin "51") (pinfunction "QSPI_SD3_51") (pintype "bidirectional"))
    )
    (net (code "52") (name "RP2040_RXD") (class "Default")
      (node (ref "U4") (pin "26") (pinfunction "U0TXD/GPIO1_26") (pintype "bidirectional"))
      (node (ref "U5") (pin "7") (pinfunction "GPIO5_7") (pintype "bidirectional"))
    )
    (net (code "53") (name "RP2040_TXD") (class "Default")
      (node (ref "U4") (pin "25") (pinfunction "U0RXD/GPIO3_25") (pintype "bidirectional"))
      (node (ref "U5") (pin "6") (pinfunction "GPIO4_6") (pintype "bidirectional"))
    )
    (net (code "54") (name "RX") (class "Default")
      (node (ref "JP1") (pin "3") (pinfunction "3_3") (pintype "passive"))
      (node (ref "U5") (pin "28") (pinfunction "GPIO17_28") (pintype "bidirectional"))
    )
    (net (code "55") (name "SCK") (class "Default")
      (node (ref "JP1") (pin "6") (pinfunction "6_6") (pintype "passive"))
      (node (ref "U5") (pin "34") (pinfunction "GPIO22_34") (pintype "bidirectional"))
    )
    (net (code "56") (name "SDI") (class "Default")
      (node (ref "JP1") (pin "4") (pinfunction "4_4") (pintype "passive"))
      (node (ref "U5") (pin "31") (pinfunction "GPIO20_31") (pintype "bidirectional"))
    )
    (net (code "57") (name "SDO") (class "Default")
      (node (ref "JP1") (pin "5") (pinfunction "5_5") (pintype "passive"))
      (node (ref "U5") (pin "35") (pinfunction "GPIO23_35") (pintype "bidirectional"))
    )
    (net (code "58") (name "SLEEP") (class "Default")
      (node (ref "R9") (pin "2") (pinfunction "2_2") (pintype "passive"))
      (node (ref "U4") (pin "8") (pinfunction "XPD_DCDC/GPIO16_8") (pintype "bidirectional"))
    )
    (net (code "59") (name "TX") (class "Default")
      (node (ref "JP1") (pin "2") (pinfunction "2_2") (pintype "passive"))
      (node (ref "U5") (pin "27") (pinfunction "GPIO16_27") (pintype "bidirectional"))
    )
    (net (code "60") (name "VBAT") (class "Default")
      (node (ref "C3") (pin "1") (pinfunction "1_1") (pintype "passive"))
      (node (ref "JP3") (pin "1") (pinfunction "1_1") (pintype "passive"))
      (node (ref "Q11") (pin "2") (pinfunction "S_2") (pintype "passive"))
      (node (ref "U3") (pin "3") (pinfunction "VBAT_3") (pintype "power_in"))
      (node (ref "X1") (pin "2") (pinfunction "2_2") (pintype "passive"))
    )
    (net (code "61") (name "VBUS") (class "Default")
      (node (ref "CHG") (pin "A") (pinfunction "A_A") (pintype "passive"))
      (node (ref "D1") (pin "A") (pinfunction "A_A") (pintype "passive"))
      (node (ref "J2") (pin "A4/B9") (pinfunction "VBUS_A4/B9") (pintype "power_in"))
      (node (ref "J2") (pin "B4/A9") (pinfunction "VBUS_B4/A9") (pintype "power_in"))
      (node (ref "JP3") (pin "3") (pinfunction "3_3") (pintype "passive"))
      (node (ref "Q11") (pin "1") (pinfunction "G_1") (pintype "passive"))
      (node (ref "R17") (pin "1") (pinfunction "1_1") (pintype "passive"))
      (node (ref "U3") (pin "4") (pinfunction "VDD_4") (pintype "power_in"))
    )
    (net (code "62") (name "WIFI_BOOT") (class "Default")
      (node (ref "U4") (pin "15") (pinfunction "GPIO0/SPICS2_15") (pintype "bidirectional"))
      (node (ref "U5") (pin "16") (pinfunction "GPIO13_16") (pintype "bidirectional"))
    )
    (net (code "63") (name "unconnected-(J2-SBU1-PadA8)") (class "Default")
      (node (ref "J2") (pin "A8") (pinfunction "SBU1_A8") (pintype "bidirectional"))
    )
    (net (code "64") (name "unconnected-(J2-SBU2-PadB8)") (class "Default")
      (node (ref "J2") (pin "B8") (pinfunction "SBU2_B8") (pintype "bidirectional"))
    )
    (net (code "65") (name "unconnected-(LED1-DO-Pad3)") (class "Default")
      (node (ref "LED1") (pin "3") (pinfunction "DO_3") (pintype "output"))
    )
    (net (code "66") (name "unconnected-(U2-P4-Pad4)") (class "Default")
      (node (ref "U2") (pin "4") (pinfunction "P4_4") (pintype "bidirectional"))
    )
    (net (code "67") (name "unconnected-(U4-GPIO4-Pad16)") (class "Default")
      (node (ref "U4") (pin "16") (pinfunction "GPIO4_16") (pintype "bidirectional"))
    )
    (net (code "68") (name "unconnected-(U4-GPIO5-Pad24)") (class "Default")
      (node (ref "U4") (pin "24") (pinfunction "GPIO5_24") (pintype "bidirectional"))
    )
    (net (code "69") (name "unconnected-(U4-MTCK{slash}GPIO13-Pad12)") (class "Default")
      (node (ref "U4") (pin "12") (pinfunction "MTCK/GPIO13_12") (pintype "bidirectional"))
    )
    (net (code "70") (name "unconnected-(U4-MTDI{slash}GPIO12-Pad10)") (class "Default")
      (node (ref "U4") (pin "10") (pinfunction "MTDI/GPIO12_10") (pintype "bidirectional"))
    )
    (net (code "71") (name "unconnected-(U4-MTMS{slash}GPIO14-Pad9)") (class "Default")
      (node (ref "U4") (pin "9") (pinfunction "MTMS/GPIO14_9") (pintype "bidirectional"))
    )
    (net (code "72") (name "unconnected-(U4-SD_CLK-Pad21)") (class "Default")
      (node (ref "U4") (pin "21") (pinfunction "SD_CLK_21") (pintype "bidirectional"))
    )
    (net (code "73") (name "unconnected-(U4-SD_CMD-Pad20)") (class "Default")
      (node (ref "U4") (pin "20") (pinfunction "SD_CMD_20") (pintype "bidirectional"))
    )
    (net (code "74") (name "unconnected-(U4-SD_D0-Pad22)") (class "Default")
      (node (ref "U4") (pin "22") (pinfunction "SD_D0_22") (pintype "bidirectional"))
    )
    (net (code "75") (name "unconnected-(U4-SD_D1-Pad23)") (class "Default")
      (node (ref "U4") (pin "23") (pinfunction "SD_D1_23") (pintype "bidirectional"))
    )
    (net (code "76") (name "unconnected-(U4-SD_D2-Pad18)") (class "Default")
      (node (ref "U4") (pin "18") (pinfunction "SD_D2_18") (pintype "bidirectional"))
    )
    (net (code "77") (name "unconnected-(U4-SD_D3-Pad19)") (class "Default")
      (node (ref "U4") (pin "19") (pinfunction "SD_D3_19") (pintype "bidirectional"))
    )
    (net (code "78") (name "unconnected-(U4-TOUT{slash}ADC-Pad6)") (class "Default")
      (node (ref "U4") (pin "6") (pinfunction "TOUT/ADC_6") (pintype "bidirectional"))
    )
    (net (code "79") (name "unconnected-(U4-VDD_RTC-Pad5)") (class "Default")
      (node (ref "U4") (pin "5") (pinfunction "VDD_RTC_5") (pintype "bidirectional"))
    )
    (net (code "80") (name "unconnected-(U5-GPIO14-Pad17)") (class "Default")
      (node (ref "U5") (pin "17") (pinfunction "GPIO14_17") (pintype "bidirectional"))
    )
    (net (code "81") (name "unconnected-(U5-GPIO15-Pad18)") (class "Default")
      (node (ref "U5") (pin "18") (pinfunction "GPIO15_18") (pintype "bidirectional"))
    )
    (net (code "82") (name "unconnected-(U5-GPIO18-Pad29)") (class "Default")
      (node (ref "U5") (pin "29") (pinfunction "GPIO18_29") (pintype "bidirectional"))
    )
    (net (code "83") (name "unconnected-(U5-GPIO24-Pad36)") (class "Default")
      (node (ref "U5") (pin "36") (pinfunction "GPIO24_36") (pintype "bidirectional"))
    )
    (net (code "84") (name "~{BOOTSEL}") (class "Default")
      (node (ref "R15") (pin "2") (pinfunction "2_2") (pintype "passive"))
      (node (ref "SW2") (pin "1") (pinfunction "P_1") (pintype "passive"))
      (node (ref "SW2") (pin "3") (pinfunction "P1_3") (pintype "passive"))
    )
    (net (code "85") (name "~{CS}") (class "Default")
      (node (ref "JP1") (pin "7") (pinfunction "7_7") (pintype "passive"))
      (node (ref "U5") (pin "32") (pinfunction "GPIO21_32") (pintype "bidirectional"))
    )
    (net (code "86") (name "~{QSPI_CS}") (class "Default")
      (node (ref "R15") (pin "1") (pinfunction "1_1") (pintype "passive"))
      (node (ref "R16") (pin "2") (pinfunction "2_2") (pintype "passive"))
      (node (ref "U1") (pin "1") (pinfunction "SSEL_1") (pintype "bidirectional"))
      (node (ref "U5") (pin "56") (pinfunction "~{QSPI_CS}_56") (pintype "bidirectional"))
    )
    (net (code "87") (name "~{RESET}") (class "Default")
      (node (ref "JP1") (pin "16") (pinfunction "16_16") (pintype "passive"))
      (node (ref "R6") (pin "1") (pinfunction "1_1") (pintype "passive"))
      (node (ref "SW1") (pin "1") (pinfunction "P_1") (pintype "passive"))
      (node (ref "SW1") (pin "3") (pinfunction "P1_3") (pintype "passive"))
      (node (ref "U5") (pin "26") (pinfunction "RUN_26") (pintype "bidirectional"))
    )
    (net (code "88") (name "~{W_RST}") (class "Default")
      (node (ref "R9") (pin "1") (pinfunction "1_1") (pintype "passive"))
      (node (ref "U4") (pin "32") (pinfunction "RSTB_32") (pintype "bidirectional"))
      (node (ref "U5") (pin "30") (pinfunction "GPIO19_30") (pintype "bidirectional"))
    )
  )
)
